# 150218_AriloTX_REV3_1_0_868MHZ_CORRECT_T.net
KiCad netlist of a schematic drawn in EAGLE
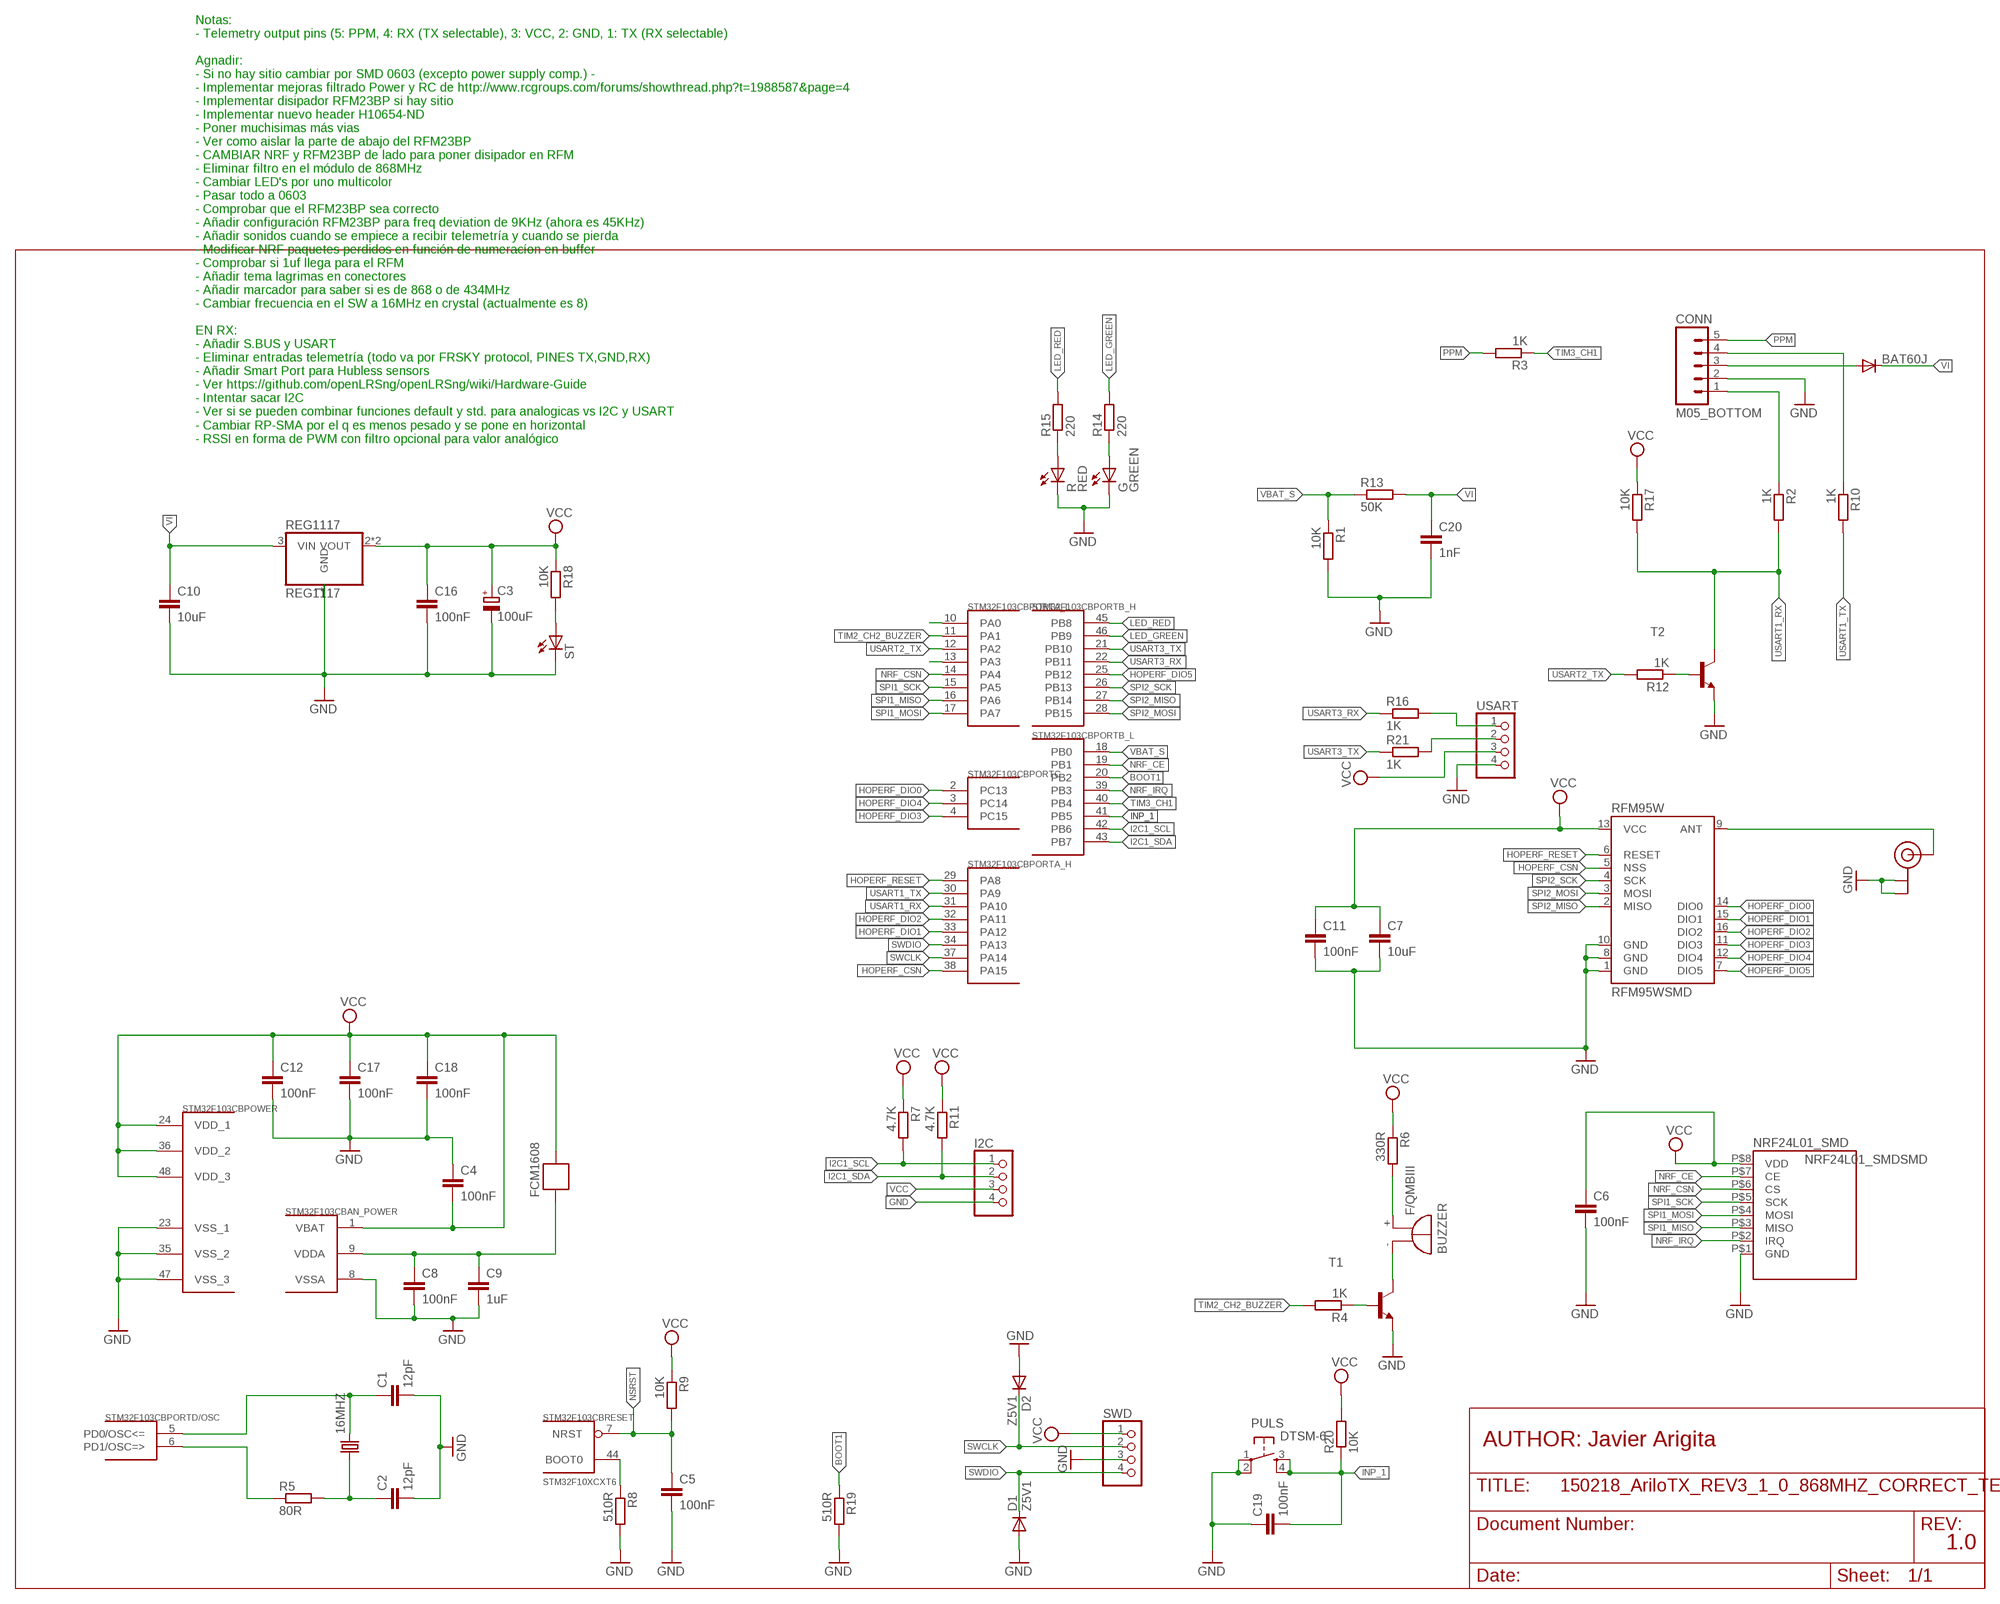
[diagram p0: schematic, sheet 1]

(export (version "E")
  (design (tool "Eeschema 10.0.6"))
  (components
    (comp (ref "16MHZ")
      (value "CRYSTAL5X3")
      (footprint "eagle-import:CRYSTAL-SMD-5X3")
      (libsource (lib "eagle-import") (part "CRYSTAL5X3"))
    )
    (comp (ref "BAT60J")
      (value "DIODE-SOD323-R")
      (footprint "eagle-import:SOD323-R")
      (libsource (lib "eagle-import") (part "DIODE-SOD323-R"))
    )
    (comp (ref "BUZZER")
      (value "F/QMBIII")
      (footprint "eagle-import:F_QMBIII")
      (libsource (lib "eagle-import") (part "F/QMBIII"))
    )
    (comp (ref "C1")
      (value "12pF")
      (footprint "eagle-import:C0603")
      (libsource (lib "eagle-import") (part "C-EUC0603"))
    )
    (comp (ref "C2")
      (value "12pF")
      (footprint "eagle-import:C0603")
      (libsource (lib "eagle-import") (part "C-EUC0603"))
    )
    (comp (ref "C3")
      (value "100uF")
      (footprint "eagle-import:SMC_B")
      (libsource (lib "eagle-import") (part "CPOL-EUSMCB"))
    )
    (comp (ref "C4")
      (value "100nF")
      (footprint "eagle-import:C0603")
      (libsource (lib "eagle-import") (part "C-EUC0603"))
    )
    (comp (ref "C5")
      (value "100nF")
      (footprint "eagle-import:C0603")
      (libsource (lib "eagle-import") (part "C-EUC0603"))
    )
    (comp (ref "C6")
      (value "100nF")
      (footprint "eagle-import:C0603")
      (libsource (lib "eagle-import") (part "C-EUC0603"))
    )
    (comp (ref "C7")
      (value "10uF")
      (footprint "eagle-import:C3216")
      (libsource (lib "eagle-import") (part "resistor_C-EUC3216"))
    )
    (comp (ref "C8")
      (value "100nF")
      (footprint "eagle-import:C0603")
      (libsource (lib "eagle-import") (part "C-EUC0603"))
    )
    (comp (ref "C9")
      (value "1uF")
      (footprint "eagle-import:C0603")
      (libsource (lib "eagle-import") (part "C-EUC0603"))
    )
    (comp (ref "C10")
      (value "10uF")
      (footprint "eagle-import:C3216")
      (libsource (lib "eagle-import") (part "resistor_C-EUC3216"))
    )
    (comp (ref "C11")
      (value "100nF")
      (footprint "eagle-import:C0603")
      (libsource (lib "eagle-import") (part "C-EUC0603"))
    )
    (comp (ref "C12")
      (value "100nF")
      (footprint "eagle-import:C0603")
      (libsource (lib "eagle-import") (part "C-EUC0603"))
    )
    (comp (ref "C16")
      (value "100nF")
      (footprint "eagle-import:C0603")
      (libsource (lib "eagle-import") (part "C-EUC0603"))
    )
    (comp (ref "C17")
      (value "100nF")
      (footprint "eagle-import:C0603")
      (libsource (lib "eagle-import") (part "C-EUC0603"))
    )
    (comp (ref "C18")
      (value "100nF")
      (footprint "eagle-import:C0603")
      (libsource (lib "eagle-import") (part "C-EUC0603"))
    )
    (comp (ref "C19")
      (value "100nF")
      (footprint "eagle-import:C0603")
      (libsource (lib "eagle-import") (part "C-EUC0603"))
    )
    (comp (ref "C20")
      (value "1nF")
      (footprint "eagle-import:C0603")
      (libsource (lib "eagle-import") (part "C-EUC0603"))
    )
    (comp (ref "CONN")
      (value "M05_BOTTOM")
      (footprint "eagle-import:M05_BOTTOM")
      (libsource (lib "eagle-import") (part "M05_BOTTOM"))
    )
    (comp (ref "D1")
      (value "Z5V1")
      (footprint "eagle-import:SOD323-R")
      (libsource (lib "eagle-import") (part "DIODE-SOD323-R"))
    )
    (comp (ref "D2")
      (value "Z5V1")
      (footprint "eagle-import:SOD323-R")
      (libsource (lib "eagle-import") (part "DIODE-SOD323-R"))
    )
    (comp (ref "FCM1608")
      (value "FERRITE-BEAD")
      (footprint "eagle-import:R0603")
      (libsource (lib "eagle-import") (part "FERRITE-BEAD"))
    )
    (comp (ref "G")
      (value "GREEN")
      (footprint "eagle-import:CHIP-LED0603")
      (libsource (lib "eagle-import") (part "LEDCHIP-LED0603"))
    )
    (comp (ref "I2C")
      (value "PINHD-1X4")
      (footprint "eagle-import:1X04")
      (libsource (lib "eagle-import") (part "PINHD-1X4"))
    )
    (comp (ref "NRF24L01_SMD")
      (value "NRF24L01_SMDSMD")
      (footprint "eagle-import:NRF24L01_SMD")
      (libsource (lib "eagle-import") (part "NRF24L01_SMDSMD"))
    )
    (comp (ref "PULS")
      (value "DTSM-6")
      (footprint "eagle-import:DTSM-6")
      (libsource (lib "eagle-import") (part "DTSM-6"))
    )
    (comp (ref "R")
      (value "RED")
      (footprint "eagle-import:CHIP-LED0603")
      (libsource (lib "eagle-import") (part "LEDCHIP-LED0603"))
    )
    (comp (ref "R1")
      (value "10K")
      (footprint "eagle-import:R0603")
      (libsource (lib "eagle-import") (part "R-EU_R0603"))
    )
    (comp (ref "R2")
      (value "1K")
      (footprint "eagle-import:R0603")
      (libsource (lib "eagle-import") (part "R-EU_R0603"))
    )
    (comp (ref "R3")
      (value "1K")
      (footprint "eagle-import:R0603")
      (libsource (lib "eagle-import") (part "R-EU_R0603"))
    )
    (comp (ref "R4")
      (value "1K")
      (footprint "eagle-import:R0603")
      (libsource (lib "eagle-import") (part "R-EU_R0603"))
    )
    (comp (ref "R5")
      (value "80R")
      (footprint "eagle-import:R0603")
      (libsource (lib "eagle-import") (part "R-EU_R0603"))
    )
    (comp (ref "R6")
      (value "330R")
      (footprint "eagle-import:R0603")
      (libsource (lib "eagle-import") (part "R-EU_R0603"))
    )
    (comp (ref "R7")
      (value "4.7K")
      (footprint "eagle-import:R0603")
      (libsource (lib "eagle-import") (part "R-EU_R0603"))
    )
    (comp (ref "R8")
      (value "510R")
      (footprint "eagle-import:R0603")
      (libsource (lib "eagle-import") (part "R-EU_R0603"))
    )
    (comp (ref "R9")
      (value "10K")
      (footprint "eagle-import:R0603")
      (libsource (lib "eagle-import") (part "R-EU_R0603"))
    )
    (comp (ref "R10")
      (value "1K")
      (footprint "eagle-import:R0603")
      (libsource (lib "eagle-import") (part "R-EU_R0603"))
    )
    (comp (ref "R11")
      (value "4.7K")
      (footprint "eagle-import:R0603")
      (libsource (lib "eagle-import") (part "R-EU_R0603"))
    )
    (comp (ref "R12")
      (value "1K")
      (footprint "eagle-import:R0603")
      (libsource (lib "eagle-import") (part "R-EU_R0603"))
    )
    (comp (ref "R13")
      (value "50K")
      (footprint "eagle-import:R0603")
      (libsource (lib "eagle-import") (part "R-EU_R0603"))
    )
    (comp (ref "R14")
      (value "220")
      (footprint "eagle-import:R0603")
      (libsource (lib "eagle-import") (part "R-EU_R0603"))
    )
    (comp (ref "R15")
      (value "220")
      (footprint "eagle-import:R0603")
      (libsource (lib "eagle-import") (part "R-EU_R0603"))
    )
    (comp (ref "R16")
      (value "1K")
      (footprint "eagle-import:R0603")
      (libsource (lib "eagle-import") (part "R-EU_R0603"))
    )
    (comp (ref "R17")
      (value "10K")
      (footprint "eagle-import:R0603")
      (libsource (lib "eagle-import") (part "R-EU_R0603"))
    )
    (comp (ref "R18")
      (value "10K")
      (footprint "eagle-import:R0603")
      (libsource (lib "eagle-import") (part "R-EU_R0603"))
    )
    (comp (ref "R19")
      (value "510R")
      (footprint "eagle-import:R0603")
      (libsource (lib "eagle-import") (part "R-EU_R0603"))
    )
    (comp (ref "R20")
      (value "10K")
      (footprint "eagle-import:R0603")
      (libsource (lib "eagle-import") (part "R-EU_R0603"))
    )
    (comp (ref "R21")
      (value "1K")
      (footprint "eagle-import:R0603")
      (libsource (lib "eagle-import") (part "R-EU_R0603"))
    )
    (comp (ref "REG1117")
      (value "REG1117")
      (footprint "eagle-import:SOT223")
      (libsource (lib "eagle-import") (part "REG1117"))
    )
    (comp (ref "RFM95W")
      (value "RFM95WSMD")
      (footprint "eagle-import:MISIEK_RFM95W_SMD")
      (libsource (lib "eagle-import") (part "MISIEK_RFM95WSMD"))
    )
    (comp (ref "ST")
      (value "LEDCHIP-LED0603")
      (footprint "eagle-import:CHIP-LED0603")
      (libsource (lib "eagle-import") (part "LEDCHIP-LED0603"))
    )
    (comp (ref "STM32F103CB")
      (value "STM32F10XCXT6")
      (footprint "eagle-import:TQFP48")
      (libsource (lib "eagle-import") (part "STM32F10XCXT6"))
    )
    (comp (ref "SWD")
      (value "PINHD-1X4")
      (footprint "eagle-import:1X04")
      (libsource (lib "eagle-import") (part "PINHD-1X4"))
    )
    (comp (ref "T1")
      (value "BC848-NPN-SOT23-BEC")
      (footprint "eagle-import:SOT23-BEC")
      (libsource (lib "eagle-import") (part "-NPN-SOT23-BECBC848"))
    )
    (comp (ref "T2")
      (value "BC848-NPN-SOT23-BEC")
      (footprint "eagle-import:SOT23-BEC")
      (libsource (lib "eagle-import") (part "-NPN-SOT23-BECBC848"))
    )
    (comp (ref "U.FL")
      (value "U.FL")
      (footprint "eagle-import:U.FL")
      (libsource (lib "eagle-import") (part "U.FL"))
    )
    (comp (ref "USART")
      (value "PINHD-1X4")
      (footprint "eagle-import:1X04")
      (libsource (lib "eagle-import") (part "PINHD-1X4"))
    )
  )
  (nets
    (net (code "1") (name "BOOT1") (class "Default")
      (node (ref "R19") (pin "1") (pinfunction "1_1") (pintype "passive"))
      (node (ref "STM32F103CB") (pin "20") (pinfunction "PB2_20") (pintype "bidirectional"))
    )
    (net (code "2") (name "GND") (class "Default")
      (node (ref "C1") (pin "2") (pinfunction "2_2") (pintype "passive"))
      (node (ref "C10") (pin "2") (pinfunction "2_2") (pintype "passive"))
      (node (ref "C11") (pin "2") (pinfunction "2_2") (pintype "passive"))
      (node (ref "C12") (pin "2") (pinfunction "2_2") (pintype "passive"))
      (node (ref "C16") (pin "2") (pinfunction "2_2") (pintype "passive"))
      (node (ref "C17") (pin "2") (pinfunction "2_2") (pintype "passive"))
      (node (ref "C18") (pin "2") (pinfunction "2_2") (pintype "passive"))
      (node (ref "C19") (pin "1") (pinfunction "1_1") (pintype "passive"))
      (node (ref "C2") (pin "2") (pinfunction "2_2") (pintype "passive"))
      (node (ref "C20") (pin "2") (pinfunction "2_2") (pintype "passive"))
      (node (ref "C3") (pin "-") (pinfunction "-_-") (pintype "passive"))
      (node (ref "C4") (pin "1") (pinfunction "1_1") (pintype "passive"))
      (node (ref "C5") (pin "2") (pinfunction "2_2") (pintype "passive"))
      (node (ref "C6") (pin "2") (pinfunction "2_2") (pintype "passive"))
      (node (ref "C7") (pin "2") (pinfunction "2_2") (pintype "passive"))
      (node (ref "C8") (pin "2") (pinfunction "2_2") (pintype "passive"))
      (node (ref "C9") (pin "2") (pinfunction "2_2") (pintype "passive"))
      (node (ref "CONN") (pin "2") (pinfunction "2_2") (pintype "passive"))
      (node (ref "D1") (pin "A") (pinfunction "A_A") (pintype "passive"))
      (node (ref "D2") (pin "A") (pinfunction "A_A") (pintype "passive"))
      (node (ref "G") (pin "C") (pinfunction "C_C") (pintype "passive"))
      (node (ref "I2C") (pin "4") (pinfunction "4_4") (pintype "passive"))
      (node (ref "NRF24L01_SMD") (pin "P$1") (pinfunction "GND_P$1") (pintype "power_in"))
      (node (ref "PULS") (pin "1") (pinfunction "1_1") (pintype "passive"))
      (node (ref "PULS") (pin "2") (pinfunction "2_2") (pintype "passive"))
      (node (ref "R") (pin "C") (pinfunction "C_C") (pintype "passive"))
      (node (ref "R1") (pin "2") (pinfunction "2_2") (pintype "passive"))
      (node (ref "R19") (pin "2") (pinfunction "2_2") (pintype "passive"))
      (node (ref "R8") (pin "2") (pinfunction "2_2") (pintype "passive"))
      (node (ref "REG1117") (pin "1") (pinfunction "GND_1") (pintype "power_in"))
      (node (ref "RFM95W") (pin "1") (pinfunction "GND_1") (pintype "power_in"))
      (node (ref "RFM95W") (pin "10") (pinfunction "GND_10") (pintype "power_in"))
      (node (ref "RFM95W") (pin "8") (pinfunction "GND_8") (pintype "power_in"))
      (node (ref "ST") (pin "C") (pinfunction "C_C") (pintype "passive"))
      (node (ref "STM32F103CB") (pin "23") (pinfunction "VSS_1_23") (pintype "power_in"))
      (node (ref "STM32F103CB") (pin "35") (pinfunction "VSS_2_35") (pintype "power_in"))
      (node (ref "STM32F103CB") (pin "47") (pinfunction "VSS_3_47") (pintype "power_in"))
      (node (ref "STM32F103CB") (pin "8") (pinfunction "VSSA_8") (pintype "power_in"))
      (node (ref "SWD") (pin "3") (pinfunction "3_3") (pintype "passive"))
      (node (ref "T1") (pin "E") (pinfunction "E_E") (pintype "passive"))
      (node (ref "T2") (pin "E") (pinfunction "E_E") (pintype "passive"))
      (node (ref "U.FL") (pin "P$1") (pinfunction "GND_P$1") (pintype "bidirectional"))
      (node (ref "U.FL") (pin "P$2") (pinfunction "GND_P$2") (pintype "bidirectional"))
      (node (ref "USART") (pin "4") (pinfunction "4_4") (pintype "passive"))
    )
    (net (code "3") (name "HOPERF_CSN") (class "Default")
      (node (ref "RFM95W") (pin "5") (pinfunction "NSS_5") (pintype "input"))
      (node (ref "STM32F103CB") (pin "38") (pinfunction "PA15_38") (pintype "bidirectional"))
    )
    (net (code "4") (name "HOPERF_DIO0") (class "Default")
      (node (ref "RFM95W") (pin "14") (pinfunction "DIO0_14") (pintype "input"))
      (node (ref "STM32F103CB") (pin "2") (pinfunction "PC13_2") (pintype "bidirectional"))
    )
    (net (code "5") (name "HOPERF_DIO1") (class "Default")
      (node (ref "RFM95W") (pin "15") (pinfunction "DIO1_15") (pintype "input"))
      (node (ref "STM32F103CB") (pin "33") (pinfunction "PA12_33") (pintype "bidirectional"))
    )
    (net (code "6") (name "HOPERF_DIO2") (class "Default")
      (node (ref "RFM95W") (pin "16") (pinfunction "DIO2_16") (pintype "input"))
      (node (ref "STM32F103CB") (pin "32") (pinfunction "PA11_32") (pintype "bidirectional"))
    )
    (net (code "7") (name "HOPERF_DIO3") (class "Default")
      (node (ref "RFM95W") (pin "11") (pinfunction "DIO3_11") (pintype "bidirectional"))
      (node (ref "STM32F103CB") (pin "4") (pinfunction "PC15_4") (pintype "bidirectional"))
    )
    (net (code "8") (name "HOPERF_DIO4") (class "Default")
      (node (ref "RFM95W") (pin "12") (pinfunction "DIO4_12") (pintype "bidirectional"))
      (node (ref "STM32F103CB") (pin "3") (pinfunction "PC14_3") (pintype "bidirectional"))
    )
    (net (code "9") (name "HOPERF_DIO5") (class "Default")
      (node (ref "RFM95W") (pin "7") (pinfunction "DIO5_7") (pintype "bidirectional"))
      (node (ref "STM32F103CB") (pin "25") (pinfunction "PB12_25") (pintype "bidirectional"))
    )
    (net (code "10") (name "HOPERF_RESET") (class "Default")
      (node (ref "RFM95W") (pin "6") (pinfunction "RESET_6") (pintype "output"))
      (node (ref "STM32F103CB") (pin "29") (pinfunction "PA8_29") (pintype "bidirectional"))
    )
    (net (code "11") (name "I2C1_SCL") (class "Default")
      (node (ref "I2C") (pin "1") (pinfunction "1_1") (pintype "passive"))
      (node (ref "R7") (pin "2") (pinfunction "2_2") (pintype "passive"))
      (node (ref "STM32F103CB") (pin "42") (pinfunction "PB6_42") (pintype "bidirectional"))
    )
    (net (code "12") (name "I2C1_SDA") (class "Default")
      (node (ref "I2C") (pin "2") (pinfunction "2_2") (pintype "passive"))
      (node (ref "R11") (pin "2") (pinfunction "2_2") (pintype "passive"))
      (node (ref "STM32F103CB") (pin "43") (pinfunction "PB7_43") (pintype "bidirectional"))
    )
    (net (code "13") (name "INP_1") (class "Default")
      (node (ref "C19") (pin "2") (pinfunction "2_2") (pintype "passive"))
      (node (ref "PULS") (pin "3") (pinfunction "3_3") (pintype "passive"))
      (node (ref "PULS") (pin "4") (pinfunction "4_4") (pintype "passive"))
      (node (ref "R20") (pin "1") (pinfunction "1_1") (pintype "passive"))
      (node (ref "STM32F103CB") (pin "41") (pinfunction "PB5_41") (pintype "bidirectional"))
    )
    (net (code "14") (name "LED_GREEN") (class "Default")
      (node (ref "R14") (pin "2") (pinfunction "2_2") (pintype "passive"))
      (node (ref "STM32F103CB") (pin "46") (pinfunction "PB9_46") (pintype "bidirectional"))
    )
    (net (code "15") (name "LED_RED") (class "Default")
      (node (ref "R15") (pin "2") (pinfunction "2_2") (pintype "passive"))
      (node (ref "STM32F103CB") (pin "45") (pinfunction "PB8_45") (pintype "bidirectional"))
    )
    (net (code "16") (name "NRF_CE") (class "Default")
      (node (ref "NRF24L01_SMD") (pin "P$7") (pinfunction "CE_P$7") (pintype "input"))
      (node (ref "STM32F103CB") (pin "19") (pinfunction "PB1_19") (pintype "bidirectional"))
    )
    (net (code "17") (name "NRF_CSN") (class "Default")
      (node (ref "NRF24L01_SMD") (pin "P$6") (pinfunction "CS_P$6") (pintype "input"))
      (node (ref "STM32F103CB") (pin "14") (pinfunction "PA4_14") (pintype "bidirectional"))
    )
    (net (code "18") (name "NRF_IRQ") (class "Default")
      (node (ref "NRF24L01_SMD") (pin "P$2") (pinfunction "IRQ_P$2") (pintype "output"))
      (node (ref "STM32F103CB") (pin "39") (pinfunction "PB3_39") (pintype "bidirectional"))
    )
    (net (code "19") (name "NSRST") (class "Default")
      (node (ref "C5") (pin "1") (pinfunction "1_1") (pintype "passive"))
      (node (ref "R9") (pin "2") (pinfunction "2_2") (pintype "passive"))
      (node (ref "STM32F103CB") (pin "7") (pinfunction "NRST_7") (pintype "input"))
    )
    (net (code "20") (name "Net-(16MHZ-2)") (class "Default")
      (node (ref "16MHZ") (pin "3") (pinfunction "2_3") (pintype "passive"))
      (node (ref "C1") (pin "1") (pinfunction "1_1") (pintype "passive"))
      (node (ref "STM32F103CB") (pin "5") (pinfunction "PD0/OSC<=_5") (pintype "bidirectional"))
    )
    (net (code "21") (name "Net-(16MHZ-Pad1)") (class "Default")
      (node (ref "16MHZ") (pin "1") (pinfunction "1_1") (pintype "passive"))
      (node (ref "C2") (pin "1") (pinfunction "1_1") (pintype "passive"))
      (node (ref "R5") (pin "2") (pinfunction "2_2") (pintype "passive"))
    )
    (net (code "22") (name "Net-(BAT60J-PadA)") (class "Default")
      (node (ref "BAT60J") (pin "A") (pinfunction "A_A") (pintype "passive"))
      (node (ref "CONN") (pin "3") (pinfunction "3_3") (pintype "passive"))
    )
    (net (code "23") (name "Net-(BUZZER-+)") (class "Default")
      (node (ref "BUZZER") (pin "-") (pinfunction "+_-") (pintype "passive"))
      (node (ref "T1") (pin "C") (pinfunction "C_C") (pintype "passive"))
    )
    (net (code "24") (name "Net-(BUZZER--)") (class "Default")
      (node (ref "BUZZER") (pin "+") (pinfunction "-_+") (pintype "passive"))
      (node (ref "R6") (pin "2") (pinfunction "2_2") (pintype "passive"))
    )
    (net (code "25") (name "Net-(CONN-Pad1)") (class "Default")
      (node (ref "CONN") (pin "1") (pinfunction "1_1") (pintype "passive"))
      (node (ref "R2") (pin "1") (pinfunction "1_1") (pintype "passive"))
    )
    (net (code "26") (name "Net-(CONN-Pad4)") (class "Default")
      (node (ref "CONN") (pin "4") (pinfunction "4_4") (pintype "passive"))
      (node (ref "R10") (pin "1") (pinfunction "1_1") (pintype "passive"))
    )
    (net (code "27") (name "Net-(FCM1608-P$2)") (class "Default")
      (node (ref "C8") (pin "1") (pinfunction "1_1") (pintype "passive"))
      (node (ref "C9") (pin "1") (pinfunction "1_1") (pintype "passive"))
      (node (ref "FCM1608") (pin "2") (pinfunction "P$2_2") (pintype "bidirectional"))
      (node (ref "STM32F103CB") (pin "9") (pinfunction "VDDA_9") (pintype "power_in"))
    )
    (net (code "28") (name "Net-(G-PadA)") (class "Default")
      (node (ref "G") (pin "A") (pinfunction "A_A") (pintype "passive"))
      (node (ref "R14") (pin "1") (pinfunction "1_1") (pintype "passive"))
    )
    (net (code "29") (name "Net-(R-PadA)") (class "Default")
      (node (ref "R") (pin "A") (pinfunction "A_A") (pintype "passive"))
      (node (ref "R15") (pin "1") (pinfunction "1_1") (pintype "passive"))
    )
    (net (code "30") (name "Net-(R4-Pad1)") (class "Default")
      (node (ref "R4") (pin "1") (pinfunction "1_1") (pintype "passive"))
      (node (ref "T1") (pin "B") (pinfunction "B_B") (pintype "passive"))
    )
    (net (code "31") (name "Net-(R12-Pad1)") (class "Default")
      (node (ref "R12") (pin "1") (pinfunction "1_1") (pintype "passive"))
      (node (ref "T2") (pin "B") (pinfunction "B_B") (pintype "passive"))
    )
    (net (code "32") (name "Net-(R16-Pad2)") (class "Default")
      (node (ref "R16") (pin "2") (pinfunction "2_2") (pintype "passive"))
      (node (ref "USART") (pin "1") (pinfunction "1_1") (pintype "passive"))
    )
    (net (code "33") (name "Net-(R18-Pad2)") (class "Default")
      (node (ref "R18") (pin "2") (pinfunction "2_2") (pintype "passive"))
      (node (ref "ST") (pin "A") (pinfunction "A_A") (pintype "passive"))
    )
    (net (code "34") (name "Net-(R21-Pad2)") (class "Default")
      (node (ref "R21") (pin "2") (pinfunction "2_2") (pintype "passive"))
      (node (ref "USART") (pin "2") (pinfunction "2_2") (pintype "passive"))
    )
    (net (code "35") (name "Net-(RFM95W-ANT)") (class "Default")
      (node (ref "RFM95W") (pin "9") (pinfunction "ANT_9") (pintype "bidirectional"))
      (node (ref "U.FL") (pin "P$3") (pinfunction "SIGNAL_P$3") (pintype "bidirectional"))
    )
    (net (code "36") (name "Net-(STM32F103CBG-PD1{slash}OSC=>)") (class "Default")
      (node (ref "R5") (pin "1") (pinfunction "1_1") (pintype "passive"))
      (node (ref "STM32F103CB") (pin "6") (pinfunction "PD1/OSC=>_6") (pintype "bidirectional"))
    )
    (net (code "37") (name "Net-(STM32F103CBI-BOOT0)") (class "Default")
      (node (ref "R8") (pin "1") (pinfunction "1_1") (pintype "passive"))
      (node (ref "STM32F103CB") (pin "44") (pinfunction "BOOT0_44") (pintype "input"))
    )
    (net (code "38") (name "PPM") (class "Default")
      (node (ref "CONN") (pin "5") (pinfunction "5_5") (pintype "passive"))
      (node (ref "R3") (pin "2") (pinfunction "2_2") (pintype "passive"))
    )
    (net (code "39") (name "SPI1_MISO") (class "Default")
      (node (ref "NRF24L01_SMD") (pin "P$3") (pinfunction "MISO_P$3") (pintype "output"))
      (node (ref "STM32F103CB") (pin "16") (pinfunction "PA6_16") (pintype "bidirectional"))
    )
    (net (code "40") (name "SPI1_MOSI") (class "Default")
      (node (ref "NRF24L01_SMD") (pin "P$4") (pinfunction "MOSI_P$4") (pintype "input"))
      (node (ref "STM32F103CB") (pin "17") (pinfunction "PA7_17") (pintype "bidirectional"))
    )
    (net (code "41") (name "SPI1_SCK") (class "Default")
      (node (ref "NRF24L01_SMD") (pin "P$5") (pinfunction "SCK_P$5") (pintype "input"))
      (node (ref "STM32F103CB") (pin "15") (pinfunction "PA5_15") (pintype "bidirectional"))
    )
    (net (code "42") (name "SPI2_MISO") (class "Default")
      (node (ref "RFM95W") (pin "2") (pinfunction "MISO_2") (pintype "output"))
      (node (ref "STM32F103CB") (pin "27") (pinfunction "PB14_27") (pintype "bidirectional"))
    )
    (net (code "43") (name "SPI2_MOSI") (class "Default")
      (node (ref "RFM95W") (pin "3") (pinfunction "MOSI_3") (pintype "input"))
      (node (ref "STM32F103CB") (pin "28") (pinfunction "PB15_28") (pintype "bidirectional"))
    )
    (net (code "44") (name "SPI2_SCK") (class "Default")
      (node (ref "RFM95W") (pin "4") (pinfunction "SCK_4") (pintype "input"))
      (node (ref "STM32F103CB") (pin "26") (pinfunction "PB13_26") (pintype "bidirectional"))
    )
    (net (code "45") (name "SWCLK") (class "Default")
      (node (ref "D2") (pin "C") (pinfunction "C_C") (pintype "passive"))
      (node (ref "STM32F103CB") (pin "37") (pinfunction "PA14_37") (pintype "bidirectional"))
      (node (ref "SWD") (pin "2") (pinfunction "2_2") (pintype "passive"))
    )
    (net (code "46") (name "SWDIO") (class "Default")
      (node (ref "D1") (pin "C") (pinfunction "C_C") (pintype "passive"))
      (node (ref "STM32F103CB") (pin "34") (pinfunction "PA13_34") (pintype "bidirectional"))
      (node (ref "SWD") (pin "4") (pinfunction "4_4") (pintype "passive"))
    )
    (net (code "47") (name "TIM2_CH2_BUZZER") (class "Default")
      (node (ref "R4") (pin "2") (pinfunction "2_2") (pintype "passive"))
      (node (ref "STM32F103CB") (pin "11") (pinfunction "PA1_11") (pintype "bidirectional"))
    )
    (net (code "48") (name "TIM3_CH1") (class "Default")
      (node (ref "R3") (pin "1") (pinfunction "1_1") (pintype "passive"))
      (node (ref "STM32F103CB") (pin "40") (pinfunction "PB4_40") (pintype "bidirectional"))
    )
    (net (code "49") (name "USART1_RX") (class "Default")
      (node (ref "R17") (pin "2") (pinfunction "2_2") (pintype "passive"))
      (node (ref "R2") (pin "2") (pinfunction "2_2") (pintype "passive"))
      (node (ref "STM32F103CB") (pin "31") (pinfunction "PA10_31") (pintype "bidirectional"))
      (node (ref "T2") (pin "C") (pinfunction "C_C") (pintype "passive"))
    )
    (net (code "50") (name "USART1_TX") (class "Default")
      (node (ref "R10") (pin "2") (pinfunction "2_2") (pintype "passive"))
      (node (ref "STM32F103CB") (pin "30") (pinfunction "PA9_30") (pintype "bidirectional"))
    )
    (net (code "51") (name "USART2_TX") (class "Default")
      (node (ref "R12") (pin "2") (pinfunction "2_2") (pintype "passive"))
      (node (ref "STM32F103CB") (pin "12") (pinfunction "PA2_12") (pintype "bidirectional"))
    )
    (net (code "52") (name "USART3_RX") (class "Default")
      (node (ref "R16") (pin "1") (pinfunction "1_1") (pintype "passive"))
      (node (ref "STM32F103CB") (pin "22") (pinfunction "PB11_22") (pintype "bidirectional"))
    )
    (net (code "53") (name "USART3_TX") (class "Default")
      (node (ref "R21") (pin "1") (pinfunction "1_1") (pintype "passive"))
      (node (ref "STM32F103CB") (pin "21") (pinfunction "PB10_21") (pintype "bidirectional"))
    )
    (net (code "54") (name "VBAT_S") (class "Default")
      (node (ref "R1") (pin "1") (pinfunction "1_1") (pintype "passive"))
      (node (ref "R13") (pin "1") (pinfunction "1_1") (pintype "passive"))
      (node (ref "STM32F103CB") (pin "18") (pinfunction "PB0_18") (pintype "bidirectional"))
    )
    (net (code "55") (name "VCC") (class "Default")
      (node (ref "C11") (pin "1") (pinfunction "1_1") (pintype "passive"))
      (node (ref "C12") (pin "1") (pinfunction "1_1") (pintype "passive"))
      (node (ref "C16") (pin "1") (pinfunction "1_1") (pintype "passive"))
      (node (ref "C17") (pin "1") (pinfunction "1_1") (pintype "passive"))
      (node (ref "C18") (pin "1") (pinfunction "1_1") (pintype "passive"))
      (node (ref "C3") (pin "+") (pinfunction "+_+") (pintype "passive"))
      (node (ref "C4") (pin "2") (pinfunction "2_2") (pintype "passive"))
      (node (ref "C6") (pin "1") (pinfunction "1_1") (pintype "passive"))
      (node (ref "C7") (pin "1") (pinfunction "1_1") (pintype "passive"))
      (node (ref "FCM1608") (pin "1") (pinfunction "P$1_1") (pintype "bidirectional"))
      (node (ref "I2C") (pin "3") (pinfunction "3_3") (pintype "passive"))
      (node (ref "NRF24L01_SMD") (pin "P$8") (pinfunction "VDD_P$8") (pintype "bidirectional"))
      (node (ref "R11") (pin "1") (pinfunction "1_1") (pintype "passive"))
      (node (ref "R17") (pin "1") (pinfunction "1_1") (pintype "passive"))
      (node (ref "R18") (pin "1") (pinfunction "1_1") (pintype "passive"))
      (node (ref "R20") (pin "2") (pinfunction "2_2") (pintype "passive"))
      (node (ref "R6") (pin "1") (pinfunction "1_1") (pintype "passive"))
      (node (ref "R7") (pin "1") (pinfunction "1_1") (pintype "passive"))
      (node (ref "R9") (pin "1") (pinfunction "1_1") (pintype "passive"))
      (node (ref "REG1117") (pin "2") (pinfunction "VOUT_2") (pintype "power_in"))
      (node (ref "REG1117") (pin "4") (pinfunction "VOUT_4") (pintype "power_in"))
      (node (ref "RFM95W") (pin "13") (pinfunction "VCC_13") (pintype "bidirectional"))
      (node (ref "STM32F103CB") (pin "1") (pinfunction "VBAT_1") (pintype "power_in"))
      (node (ref "STM32F103CB") (pin "24") (pinfunction "VDD_1_24") (pintype "power_in"))
      (node (ref "STM32F103CB") (pin "36") (pinfunction "VDD_2_36") (pintype "power_in"))
      (node (ref "STM32F103CB") (pin "48") (pinfunction "VDD_3_48") (pintype "power_in"))
      (node (ref "SWD") (pin "1") (pinfunction "1_1") (pintype "passive"))
      (node (ref "USART") (pin "3") (pinfunction "3_3") (pintype "passive"))
    )
    (net (code "56") (name "VI") (class "Default")
      (node (ref "BAT60J") (pin "C") (pinfunction "C_C") (pintype "passive"))
      (node (ref "C10") (pin "1") (pinfunction "1_1") (pintype "passive"))
      (node (ref "C20") (pin "1") (pinfunction "1_1") (pintype "passive"))
      (node (ref "R13") (pin "2") (pinfunction "2_2") (pintype "passive"))
      (node (ref "REG1117") (pin "3") (pinfunction "VIN_3") (pintype "input"))
    )
    (net (code "57") (name "unconnected-(STM32F103CBC-PA0-Pad10)") (class "Default")
      (node (ref "STM32F103CB") (pin "10") (pinfunction "PA0_10") (pintype "bidirectional"))
    )
    (net (code "58") (name "unconnected-(STM32F103CBC-PA3-Pad13)") (class "Default")
      (node (ref "STM32F103CB") (pin "13") (pinfunction "PA3_13") (pintype "bidirectional"))
    )
  )
)
